# MINIRACER-FMU.net
KiCad netlist of a schematic drawn in Altium Designer
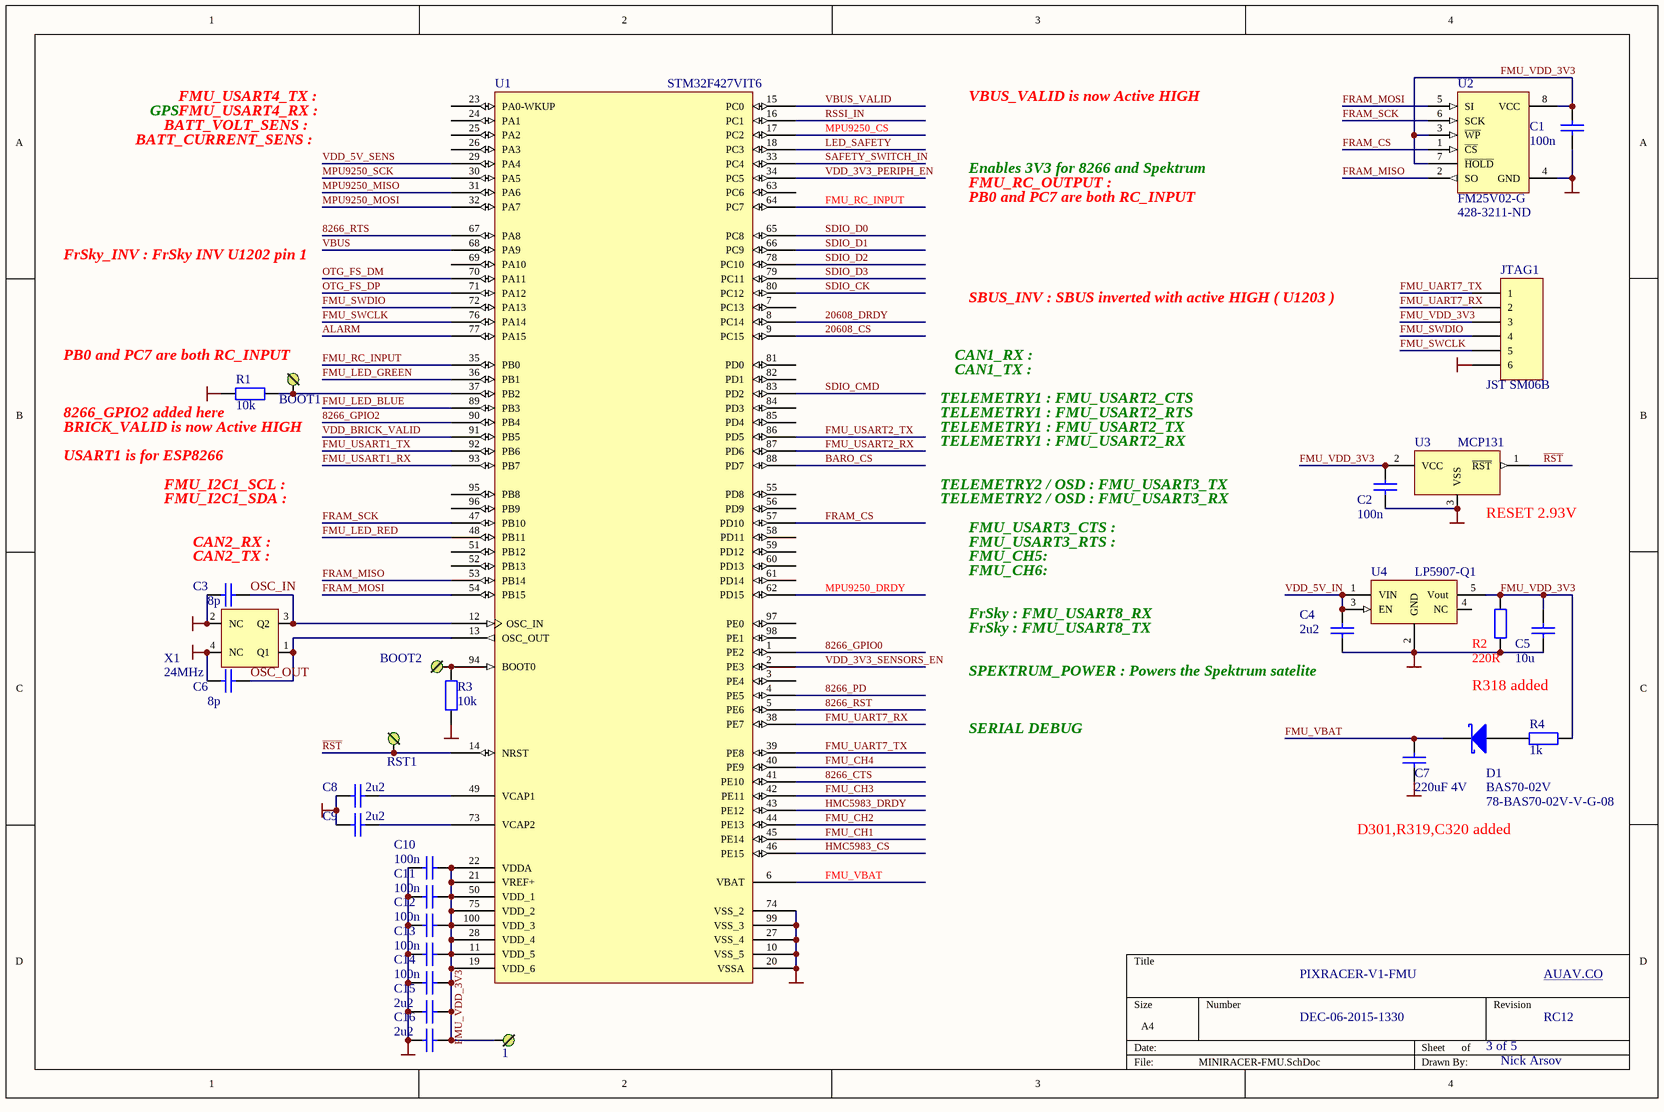
[diagram p0: MINIRACER-FMU.SchDoc]

(export (version "E")
  (design (tool "Eeschema 10.0.6"))
  (components
    (comp (ref "1") (value "3V3") (footprint "PAD1") (libsource (lib "My_Altium") (part "PLUG")))
    (comp (ref "BOOT1") (value "BOOT1") (footprint "PAD1") (libsource (lib "My_Altium") (part "PLUG")))
    (comp (ref "BOOT2") (value "BOOT") (footprint "PAD1") (libsource (lib "My_Altium") (part "PLUG")))
    (comp (ref "C1")
      (value "100n")
      (footprint "0402A")
      (description "Capacitor")
      (fields (field (name "PUBLISHER") "Altium Limited"))
      (libsource (lib "Miscellaneous Devices") (part "Cap"))
    )
    (comp (ref "C2")
      (value "100n")
      (footprint "0402A")
      (description "Capacitor")
      (fields (field (name "PUBLISHER") "Altium Limited"))
      (libsource (lib "Miscellaneous Devices") (part "Cap"))
    )
    (comp (ref "C3")
      (value "8p")
      (footprint "0603A")
      (description "Capacitor")
      (fields (field (name "PUBLISHER") "Altium Limited"))
      (libsource (lib "Miscellaneous Devices") (part "Cap"))
    )
    (comp (ref "C4")
      (value "2u2")
      (footprint "0603A")
      (description "Capacitor")
      (fields (field (name "PUBLISHER") "Altium Limited"))
      (libsource (lib "Miscellaneous Devices") (part "Cap"))
    )
    (comp (ref "C5")
      (value "10u")
      (footprint "0603A")
      (description "Capacitor")
      (fields (field (name "PUBLISHER") "Altium Limited"))
      (libsource (lib "Miscellaneous Devices") (part "Cap"))
    )
    (comp (ref "C6")
      (value "8p")
      (footprint "0603A")
      (description "Capacitor")
      (fields (field (name "PUBLISHER") "Altium Limited"))
      (libsource (lib "Miscellaneous Devices") (part "Cap"))
    )
    (comp (ref "C7")
      (value "220uF 4V")
      (footprint "1206A")
      (description "Capacitor")
      (fields (field (name "PUBLISHER") "Altium Limited"))
      (libsource (lib "Miscellaneous Devices") (part "Cap"))
    )
    (comp (ref "C8")
      (value "2u2")
      (footprint "0402A")
      (description "Capacitor")
      (fields (field (name "PUBLISHER") "Altium Limited"))
      (libsource (lib "Miscellaneous Devices") (part "Cap"))
    )
    (comp (ref "C9")
      (value "2u2")
      (footprint "0402A")
      (description "Capacitor")
      (fields (field (name "PUBLISHER") "Altium Limited"))
      (libsource (lib "Miscellaneous Devices") (part "Cap"))
    )
    (comp (ref "C10")
      (value "100n")
      (footprint "0402A")
      (description "Capacitor")
      (fields (field (name "PUBLISHER") "Altium Limited"))
      (libsource (lib "Miscellaneous Devices") (part "Cap"))
    )
    (comp (ref "C11")
      (value "100n")
      (footprint "0402A")
      (description "Capacitor")
      (fields (field (name "PUBLISHER") "Altium Limited"))
      (libsource (lib "Miscellaneous Devices") (part "Cap"))
    )
    (comp (ref "C12")
      (value "100n")
      (footprint "0402A")
      (description "Capacitor")
      (fields (field (name "PUBLISHER") "Altium Limited"))
      (libsource (lib "Miscellaneous Devices") (part "Cap"))
    )
    (comp (ref "C13")
      (value "100n")
      (footprint "0402A")
      (description "Capacitor")
      (fields (field (name "PUBLISHER") "Altium Limited"))
      (libsource (lib "Miscellaneous Devices") (part "Cap"))
    )
    (comp (ref "C14")
      (value "100n")
      (footprint "0402A")
      (description "Capacitor")
      (fields (field (name "PUBLISHER") "Altium Limited"))
      (libsource (lib "Miscellaneous Devices") (part "Cap"))
    )
    (comp (ref "C15")
      (value "2u2")
      (footprint "0402A")
      (description "Capacitor")
      (fields (field (name "PUBLISHER") "Altium Limited"))
      (libsource (lib "Miscellaneous Devices") (part "Cap"))
    )
    (comp (ref "C16")
      (value "2u2")
      (footprint "0402A")
      (description "Capacitor")
      (fields (field (name "PUBLISHER") "Altium Limited"))
      (libsource (lib "Miscellaneous Devices") (part "Cap"))
    )
    (comp (ref "D1")
      (value "BAS70-02V")
      (footprint "SOD-523")
      (description "Schottky Diode")
      (fields (field (name "MOUSER") "78-BAS70-02V-V-G-08") (field (name "PUBLISHER") "Altium Limited"))
      (libsource (lib "Miscellaneous Devices") (part "D Schottky"))
    )
    (comp (ref "JTAG1")
      (value "JST SM06B")
      (footprint "HDR1X6")
      (description "Header, 6-Pin")
      (fields (field (name "PUBLISHER") "Altium Limited"))
      (libsource (lib "Miscellaneous Connectors") (part "Header 6"))
    )
    (comp (ref "R1")
      (value "10k")
      (footprint "0402A")
      (description "Resistor")
      (fields (field (name "PUBLISHER") "Altium Limited"))
      (libsource (lib "Miscellaneous Devices") (part "Res2"))
    )
    (comp (ref "R2")
      (value "220R")
      (footprint "0603A")
      (description "Resistor")
      (fields (field (name "PUBLISHER") "Altium Limited"))
      (libsource (lib "") (part "Res2_1"))
    )
    (comp (ref "R3")
      (value "10k")
      (footprint "0402A")
      (description "Resistor")
      (fields (field (name "PUBLISHER") "Altium Limited"))
      (libsource (lib "") (part "Res2_2"))
    )
    (comp (ref "R4")
      (value "1k")
      (footprint "0603A")
      (description "Resistor")
      (fields (field (name "PUBLISHER") "Altium Limited"))
      (libsource (lib "") (part "Res2_3"))
    )
    (comp (ref "RST1") (value "BOOT") (footprint "PAD1") (libsource (lib "My_Altium") (part "PLUG")))
    (comp (ref "U1")
      (value "STM32F427VIT6")
      (footprint "LQFP100_L")
      (description "STM32 ARM-based 32-bit MCU with 64 Kbytes Flash, 100-pin LQFP, Industrial Temperature")
      (fields (field (name "PUBLISHER") "Altium Limited"))
      (libsource (lib "ST Microcontroller 32-Bit STM32") (part "STM32F103VBT6"))
    )
    (comp (ref "U2")
      (value "FM25V02-G")
      (footprint "SO-8_N")
      (fields (field (name "SUPPLIER PART NUMBER") "428-3211-ND"))
      (libsource (lib "My_Altium") (part "AT45DB161D-MU"))
    )
    (comp (ref "U3") (value "MCP131") (footprint "SOT-323") (libsource (lib "My_Altium") (part "MCP102")))
    (comp (ref "U4")
      (value "LP5907-Q1")
      (footprint "SOT23-5")
      (libsource (lib "My_Altium") (part "LP5907-Q1"))
    )
    (comp (ref "X1")
      (value "24MHz")
      (footprint "Crystal_2.5x2")
      (libsource (lib "My_Altium") (part "Crystal_4pin"))
    )
  )
  (nets
    (net (code "1") (name "/8266_CTS") (class "Default")
      (node (ref "U1") (pin "41") (pinfunction "PE10_41") (pintype "bidirectional"))
    )
    (net (code "2") (name "/8266_GPIO0") (class "Default")
      (node (ref "U1") (pin "1") (pinfunction "PE2_1") (pintype "bidirectional"))
    )
    (net (code "3") (name "/8266_GPIO2") (class "Default")
      (node (ref "U1") (pin "90") (pinfunction "PB4_90") (pintype "bidirectional"))
    )
    (net (code "4") (name "/8266_PD") (class "Default")
      (node (ref "U1") (pin "4") (pinfunction "PE5_4") (pintype "bidirectional"))
    )
    (net (code "5") (name "/8266_RST") (class "Default")
      (node (ref "U1") (pin "5") (pinfunction "PE6_5") (pintype "bidirectional"))
    )
    (net (code "6") (name "/8266_RTS") (class "Default")
      (node (ref "U1") (pin "67") (pinfunction "PA8_67") (pintype "bidirectional"))
    )
    (net (code "7") (name "/20608_CS") (class "Default")
      (node (ref "U1") (pin "9") (pinfunction "PC15_9") (pintype "bidirectional"))
    )
    (net (code "8") (name "/20608_DRDY") (class "Default")
      (node (ref "U1") (pin "8") (pinfunction "PC14_8") (pintype "bidirectional"))
    )
    (net (code "9") (name "/ALARM") (class "Default")
      (node (ref "U1") (pin "77") (pinfunction "PA15_77") (pintype "bidirectional"))
    )
    (net (code "10") (name "/BARO_CS") (class "Default")
      (node (ref "U1") (pin "88") (pinfunction "PD7_88") (pintype "bidirectional"))
    )
    (net (code "11") (name "/FMU_CH1") (class "Default")
      (node (ref "U1") (pin "45") (pinfunction "PE14_45") (pintype "bidirectional"))
    )
    (net (code "12") (name "/FMU_CH2") (class "Default")
      (node (ref "U1") (pin "44") (pinfunction "PE13_44") (pintype "bidirectional"))
    )
    (net (code "13") (name "/FMU_CH3") (class "Default")
      (node (ref "U1") (pin "42") (pinfunction "PE11_42") (pintype "bidirectional"))
    )
    (net (code "14") (name "/FMU_CH4") (class "Default")
      (node (ref "U1") (pin "40") (pinfunction "PE9_40") (pintype "bidirectional"))
    )
    (net (code "15") (name "/FMU_LED_BLUE") (class "Default")
      (node (ref "U1") (pin "89") (pinfunction "PB3_89") (pintype "bidirectional"))
    )
    (net (code "16") (name "/FMU_LED_GREEN") (class "Default")
      (node (ref "U1") (pin "36") (pinfunction "PB1_36") (pintype "bidirectional"))
    )
    (net (code "17") (name "/FMU_LED_RED") (class "Default")
      (node (ref "U1") (pin "48") (pinfunction "PB11_48") (pintype "bidirectional"))
    )
    (net (code "18") (name "/FMU_RC_INPUT") (class "Default")
      (node (ref "U1") (pin "35") (pinfunction "PB0_35") (pintype "bidirectional"))
      (node (ref "U1") (pin "64") (pinfunction "PC7_64") (pintype "bidirectional"))
    )
    (net (code "19") (name "/FMU_SWCLK") (class "Default")
      (node (ref "JTAG1") (pin "5") (pinfunction "5_5") (pintype "passive"))
      (node (ref "U1") (pin "76") (pinfunction "PA14_76") (pintype "bidirectional"))
    )
    (net (code "20") (name "/FMU_SWDIO") (class "Default")
      (node (ref "JTAG1") (pin "4") (pinfunction "4_4") (pintype "passive"))
      (node (ref "U1") (pin "72") (pinfunction "PA13_72") (pintype "bidirectional"))
    )
    (net (code "21") (name "/FMU_UART7_RX") (class "Default")
      (node (ref "JTAG1") (pin "2") (pinfunction "2_2") (pintype "passive"))
      (node (ref "U1") (pin "38") (pinfunction "PE7_38") (pintype "bidirectional"))
    )
    (net (code "22") (name "/FMU_UART7_TX") (class "Default")
      (node (ref "JTAG1") (pin "1") (pinfunction "1_1") (pintype "passive"))
      (node (ref "U1") (pin "39") (pinfunction "PE8_39") (pintype "bidirectional"))
    )
    (net (code "23") (name "/FMU_USART1_RX") (class "Default")
      (node (ref "U1") (pin "93") (pinfunction "PB7_93") (pintype "bidirectional"))
    )
    (net (code "24") (name "/FMU_USART1_TX") (class "Default")
      (node (ref "U1") (pin "92") (pinfunction "PB6_92") (pintype "bidirectional"))
    )
    (net (code "25") (name "/FMU_USART2_RX") (class "Default")
      (node (ref "U1") (pin "87") (pinfunction "PD6_87") (pintype "bidirectional"))
    )
    (net (code "26") (name "/FMU_USART2_TX") (class "Default")
      (node (ref "U1") (pin "86") (pinfunction "PD5_86") (pintype "bidirectional"))
    )
    (net (code "27") (name "/FMU_VBAT") (class "Default")
      (node (ref "C7") (pin "2") (pinfunction "2_2") (pintype "passive"))
      (node (ref "D1") (pin "2") (pinfunction "K_2") (pintype "passive"))
      (node (ref "U1") (pin "6") (pinfunction "VBAT_6") (pintype "power_in"))
    )
    (net (code "28") (name "/FMU_VDD_3V3") (class "Default")
      (node (ref "1") (pin "1") (pintype "passive"))
      (node (ref "C1") (pin "2") (pinfunction "2_2") (pintype "passive"))
      (node (ref "C10") (pin "2") (pinfunction "2_2") (pintype "passive"))
      (node (ref "C11") (pin "2") (pinfunction "2_2") (pintype "passive"))
      (node (ref "C12") (pin "2") (pinfunction "2_2") (pintype "passive"))
      (node (ref "C13") (pin "2") (pinfunction "2_2") (pintype "passive"))
      (node (ref "C14") (pin "2") (pinfunction "2_2") (pintype "passive"))
      (node (ref "C15") (pin "2") (pinfunction "2_2") (pintype "passive"))
      (node (ref "C16") (pin "2") (pinfunction "2_2") (pintype "passive"))
      (node (ref "C2") (pin "2") (pinfunction "2_2") (pintype "passive"))
      (node (ref "C5") (pin "2") (pinfunction "2_2") (pintype "passive"))
      (node (ref "JTAG1") (pin "3") (pinfunction "3_3") (pintype "passive"))
      (node (ref "R2") (pin "2") (pinfunction "2_2") (pintype "passive"))
      (node (ref "R4") (pin "1") (pinfunction "1_1") (pintype "passive"))
      (node (ref "U1") (pin "100") (pinfunction "VDD_3_100") (pintype "power_in"))
      (node (ref "U1") (pin "11") (pinfunction "VDD_5_11") (pintype "power_in"))
      (node (ref "U1") (pin "19") (pinfunction "VDD_6_19") (pintype "power_in"))
      (node (ref "U1") (pin "21") (pinfunction "VREF+_21") (pintype "power_in"))
      (node (ref "U1") (pin "22") (pinfunction "VDDA_22") (pintype "power_in"))
      (node (ref "U1") (pin "28") (pinfunction "VDD_4_28") (pintype "power_in"))
      (node (ref "U1") (pin "50") (pinfunction "VDD_1_50") (pintype "power_in"))
      (node (ref "U1") (pin "75") (pinfunction "VDD_2_75") (pintype "power_in"))
      (node (ref "U2") (pin "3") (pinfunction "~{WP}_3") (pintype "input"))
      (node (ref "U2") (pin "7") (pinfunction "~{HOLD}_7") (pintype "passive"))
      (node (ref "U2") (pin "8") (pinfunction "VCC_8") (pintype "power_in"))
      (node (ref "U3") (pin "2") (pinfunction "VCC_2") (pintype "power_in"))
      (node (ref "U4") (pin "5") (pinfunction "Vout_5") (pintype "power_in"))
    )
    (net (code "29") (name "/FRAM_CS") (class "Default")
      (node (ref "U1") (pin "57") (pinfunction "PD10_57") (pintype "bidirectional"))
      (node (ref "U2") (pin "1") (pinfunction "~{CS}_1") (pintype "input"))
    )
    (net (code "30") (name "/FRAM_MISO") (class "Default")
      (node (ref "U1") (pin "53") (pinfunction "PB14_53") (pintype "bidirectional"))
      (node (ref "U2") (pin "2") (pinfunction "SO_2") (pintype "output"))
    )
    (net (code "31") (name "/FRAM_MOSI") (class "Default")
      (node (ref "U1") (pin "54") (pinfunction "PB15_54") (pintype "bidirectional"))
      (node (ref "U2") (pin "5") (pinfunction "SI_5") (pintype "input"))
    )
    (net (code "32") (name "/FRAM_SCK") (class "Default")
      (node (ref "U1") (pin "47") (pinfunction "PB10_47") (pintype "bidirectional"))
      (node (ref "U2") (pin "6") (pinfunction "SCK_6") (pintype "input"))
    )
    (net (code "33") (name "/HMC5983_CS") (class "Default")
      (node (ref "U1") (pin "46") (pinfunction "PE15_46") (pintype "bidirectional"))
    )
    (net (code "34") (name "/HMC5983_DRDY") (class "Default")
      (node (ref "U1") (pin "43") (pinfunction "PE12_43") (pintype "bidirectional"))
    )
    (net (code "35") (name "/LED_SAFETY") (class "Default")
      (node (ref "U1") (pin "18") (pinfunction "PC3_18") (pintype "bidirectional"))
    )
    (net (code "36") (name "/MPU9250_CS") (class "Default")
      (node (ref "U1") (pin "17") (pinfunction "PC2_17") (pintype "bidirectional"))
    )
    (net (code "37") (name "/MPU9250_DRDY") (class "Default")
      (node (ref "U1") (pin "62") (pinfunction "PD15_62") (pintype "bidirectional"))
    )
    (net (code "38") (name "/MPU9250_MISO") (class "Default")
      (node (ref "U1") (pin "31") (pinfunction "PA6_31") (pintype "bidirectional"))
    )
    (net (code "39") (name "/MPU9250_MOSI") (class "Default")
      (node (ref "U1") (pin "32") (pinfunction "PA7_32") (pintype "bidirectional"))
    )
    (net (code "40") (name "/MPU9250_SCK") (class "Default")
      (node (ref "U1") (pin "30") (pinfunction "PA5_30") (pintype "bidirectional"))
    )
    (net (code "41") (name "/OSC_IN") (class "Default")
      (node (ref "C3") (pin "2") (pinfunction "2_2") (pintype "passive"))
      (node (ref "U1") (pin "12") (pinfunction "OSC_IN_12") (pintype "input"))
      (node (ref "X1") (pin "3") (pinfunction "Q2_3") (pintype "passive"))
    )
    (net (code "42") (name "/OSC_OUT") (class "Default")
      (node (ref "C6") (pin "2") (pinfunction "2_2") (pintype "passive"))
      (node (ref "U1") (pin "13") (pinfunction "OSC_OUT_13") (pintype "output"))
      (node (ref "X1") (pin "1") (pinfunction "Q1_1") (pintype "passive"))
    )
    (net (code "43") (name "/OTG_FS_DM") (class "Default")
      (node (ref "U1") (pin "70") (pinfunction "PA11_70") (pintype "bidirectional"))
    )
    (net (code "44") (name "/OTG_FS_DP") (class "Default")
      (node (ref "U1") (pin "71") (pinfunction "PA12_71") (pintype "bidirectional"))
    )
    (net (code "45") (name "/RSSI_IN") (class "Default")
      (node (ref "U1") (pin "16") (pinfunction "PC1_16") (pintype "bidirectional"))
    )
    (net (code "46") (name "/SAFETY_SWITCH_IN") (class "Default")
      (node (ref "U1") (pin "33") (pinfunction "PC4_33") (pintype "bidirectional"))
    )
    (net (code "47") (name "/SDIO_CK") (class "Default")
      (node (ref "U1") (pin "80") (pinfunction "PC12_80") (pintype "bidirectional"))
    )
    (net (code "48") (name "/SDIO_CMD") (class "Default")
      (node (ref "U1") (pin "83") (pinfunction "PD2_83") (pintype "bidirectional"))
    )
    (net (code "49") (name "/SDIO_D0") (class "Default")
      (node (ref "U1") (pin "65") (pinfunction "PC8_65") (pintype "bidirectional"))
    )
    (net (code "50") (name "/SDIO_D1") (class "Default")
      (node (ref "U1") (pin "66") (pinfunction "PC9_66") (pintype "bidirectional"))
    )
    (net (code "51") (name "/SDIO_D2") (class "Default")
      (node (ref "U1") (pin "78") (pinfunction "PC10_78") (pintype "bidirectional"))
    )
    (net (code "52") (name "/SDIO_D3") (class "Default")
      (node (ref "U1") (pin "79") (pinfunction "PC11_79") (pintype "bidirectional"))
    )
    (net (code "53") (name "/VBUS") (class "Default")
      (node (ref "U1") (pin "68") (pinfunction "PA9_68") (pintype "bidirectional"))
    )
    (net (code "54") (name "/VBUS_VALID") (class "Default")
      (node (ref "U1") (pin "15") (pinfunction "PC0_15") (pintype "bidirectional"))
    )
    (net (code "55") (name "/VDD_3V3_PERIPH_EN") (class "Default")
      (node (ref "U1") (pin "34") (pinfunction "PC5_34") (pintype "bidirectional"))
    )
    (net (code "56") (name "/VDD_3V3_SENSORS_EN") (class "Default")
      (node (ref "U1") (pin "2") (pinfunction "PE3_2") (pintype "bidirectional"))
    )
    (net (code "57") (name "/VDD_5V_IN") (class "Default")
      (node (ref "C4") (pin "2") (pinfunction "2_2") (pintype "passive"))
      (node (ref "U4") (pin "1") (pinfunction "VIN_1") (pintype "power_in"))
      (node (ref "U4") (pin "3") (pinfunction "EN_3") (pintype "input"))
    )
    (net (code "58") (name "/VDD_5V_SENS") (class "Default")
      (node (ref "U1") (pin "29") (pinfunction "PA4_29") (pintype "bidirectional"))
    )
    (net (code "59") (name "/VDD_BRICK_VALID") (class "Default")
      (node (ref "U1") (pin "91") (pinfunction "PB5_91") (pintype "bidirectional"))
    )
    (net (code "60") (name "/~{RST}") (class "Default")
      (node (ref "RST1") (pin "1") (pintype "passive"))
      (node (ref "U1") (pin "14") (pinfunction "NRST_14") (pintype "bidirectional"))
      (node (ref "U3") (pin "1") (pinfunction "~{RST}_1") (pintype "output"))
    )
    (net (code "61") (name "GND") (class "Default")
      (node (ref "C1") (pin "1") (pinfunction "1_1") (pintype "passive"))
      (node (ref "C10") (pin "1") (pinfunction "1_1") (pintype "passive"))
      (node (ref "C11") (pin "1") (pinfunction "1_1") (pintype "passive"))
      (node (ref "C12") (pin "1") (pinfunction "1_1") (pintype "passive"))
      (node (ref "C13") (pin "1") (pinfunction "1_1") (pintype "passive"))
      (node (ref "C14") (pin "1") (pinfunction "1_1") (pintype "passive"))
      (node (ref "C15") (pin "1") (pinfunction "1_1") (pintype "passive"))
      (node (ref "C16") (pin "1") (pinfunction "1_1") (pintype "passive"))
      (node (ref "C2") (pin "1") (pinfunction "1_1") (pintype "passive"))
      (node (ref "C3") (pin "1") (pinfunction "1_1") (pintype "passive"))
      (node (ref "C4") (pin "1") (pinfunction "1_1") (pintype "passive"))
      (node (ref "C5") (pin "1") (pinfunction "1_1") (pintype "passive"))
      (node (ref "C6") (pin "1") (pinfunction "1_1") (pintype "passive"))
      (node (ref "C7") (pin "1") (pinfunction "1_1") (pintype "passive"))
      (node (ref "C8") (pin "2") (pinfunction "2_2") (pintype "passive"))
      (node (ref "C9") (pin "2") (pinfunction "2_2") (pintype "passive"))
      (node (ref "JTAG1") (pin "6") (pinfunction "6_6") (pintype "passive"))
      (node (ref "R1") (pin "1") (pinfunction "1_1") (pintype "passive"))
      (node (ref "R2") (pin "1") (pinfunction "1_1") (pintype "passive"))
      (node (ref "R3") (pin "2") (pinfunction "2_2") (pintype "passive"))
      (node (ref "U1") (pin "10") (pinfunction "VSS_5_10") (pintype "power_in"))
      (node (ref "U1") (pin "20") (pinfunction "VSSA_20") (pintype "power_in"))
      (node (ref "U1") (pin "27") (pinfunction "VSS_4_27") (pintype "power_in"))
      (node (ref "U1") (pin "74") (pinfunction "VSS_2_74") (pintype "power_in"))
      (node (ref "U1") (pin "99") (pinfunction "VSS_3_99") (pintype "power_in"))
      (node (ref "U2") (pin "4") (pinfunction "GND_4") (pintype "power_in"))
      (node (ref "U3") (pin "3") (pinfunction "VSS_3") (pintype "power_in"))
      (node (ref "U4") (pin "2") (pinfunction "GND_2") (pintype "power_in"))
      (node (ref "X1") (pin "2") (pinfunction "NC_2") (pintype "passive"))
      (node (ref "X1") (pin "4") (pinfunction "NC_4") (pintype "passive"))
    )
    (net (code "62") (name "Net-(D1-A)") (class "Default")
      (node (ref "D1") (pin "1") (pinfunction "A_1") (pintype "passive"))
      (node (ref "R4") (pin "2") (pinfunction "2_2") (pintype "passive"))
    )
    (net (code "63") (name "Net-(U1-BOOT0)") (class "Default")
      (node (ref "BOOT2") (pin "1") (pintype "passive"))
      (node (ref "R3") (pin "1") (pinfunction "1_1") (pintype "passive"))
      (node (ref "U1") (pin "94") (pinfunction "BOOT0_94") (pintype "input"))
    )
    (net (code "64") (name "Net-(U1-PB2)") (class "Default")
      (node (ref "BOOT1") (pin "1") (pintype "passive"))
      (node (ref "R1") (pin "2") (pinfunction "2_2") (pintype "passive"))
      (node (ref "U1") (pin "37") (pinfunction "PB2_37") (pintype "bidirectional"))
    )
    (net (code "65") (name "Net-(U1-VCAP1)") (class "Default")
      (node (ref "C8") (pin "1") (pinfunction "1_1") (pintype "passive"))
      (node (ref "U1") (pin "49") (pinfunction "VCAP1_49") (pintype "passive"))
    )
    (net (code "66") (name "Net-(U1-VCAP2)") (class "Default")
      (node (ref "C9") (pin "1") (pinfunction "1_1") (pintype "passive"))
      (node (ref "U1") (pin "73") (pinfunction "VCAP2_73") (pintype "passive"))
    )
    (net (code "67") (name "unconnected-(U1-PA0-WKUP-Pad23)") (class "Default")
      (node (ref "U1") (pin "23") (pinfunction "PA0-WKUP_23") (pintype "bidirectional"))
    )
    (net (code "68") (name "unconnected-(U1-PA1-Pad24)") (class "Default")
      (node (ref "U1") (pin "24") (pinfunction "PA1_24") (pintype "bidirectional"))
    )
    (net (code "69") (name "unconnected-(U1-PA2-Pad25)") (class "Default")
      (node (ref "U1") (pin "25") (pinfunction "PA2_25") (pintype "bidirectional"))
    )
    (net (code "70") (name "unconnected-(U1-PA3-Pad26)") (class "Default")
      (node (ref "U1") (pin "26") (pinfunction "PA3_26") (pintype "bidirectional"))
    )
    (net (code "71") (name "unconnected-(U1-PA10-Pad69)") (class "Default")
      (node (ref "U1") (pin "69") (pinfunction "PA10_69") (pintype "bidirectional"))
    )
    (net (code "72") (name "unconnected-(U1-PB8-Pad95)") (class "Default")
      (node (ref "U1") (pin "95") (pinfunction "PB8_95") (pintype "bidirectional"))
    )
    (net (code "73") (name "unconnected-(U1-PB9-Pad96)") (class "Default")
      (node (ref "U1") (pin "96") (pinfunction "PB9_96") (pintype "bidirectional"))
    )
    (net (code "74") (name "unconnected-(U1-PB12-Pad51)") (class "Default")
      (node (ref "U1") (pin "51") (pinfunction "PB12_51") (pintype "bidirectional"))
    )
    (net (code "75") (name "unconnected-(U1-PB13-Pad52)") (class "Default")
      (node (ref "U1") (pin "52") (pinfunction "PB13_52") (pintype "bidirectional"))
    )
    (net (code "76") (name "unconnected-(U1-PC6-Pad63)") (class "Default")
      (node (ref "U1") (pin "63") (pinfunction "PC6_63") (pintype "bidirectional"))
    )
    (net (code "77") (name "unconnected-(U1-PC13-Pad7)") (class "Default")
      (node (ref "U1") (pin "7") (pinfunction "PC13_7") (pintype "bidirectional"))
    )
    (net (code "78") (name "unconnected-(U1-PD0-Pad81)") (class "Default")
      (node (ref "U1") (pin "81") (pinfunction "PD0_81") (pintype "bidirectional"))
    )
    (net (code "79") (name "unconnected-(U1-PD1-Pad82)") (class "Default")
      (node (ref "U1") (pin "82") (pinfunction "PD1_82") (pintype "bidirectional"))
    )
    (net (code "80") (name "unconnected-(U1-PD3-Pad84)") (class "Default")
      (node (ref "U1") (pin "84") (pinfunction "PD3_84") (pintype "bidirectional"))
    )
    (net (code "81") (name "unconnected-(U1-PD4-Pad85)") (class "Default")
      (node (ref "U1") (pin "85") (pinfunction "PD4_85") (pintype "bidirectional"))
    )
    (net (code "82") (name "unconnected-(U1-PD8-Pad55)") (class "Default")
      (node (ref "U1") (pin "55") (pinfunction "PD8_55") (pintype "bidirectional"))
    )
    (net (code "83") (name "unconnected-(U1-PD9-Pad56)") (class "Default")
      (node (ref "U1") (pin "56") (pinfunction "PD9_56") (pintype "bidirectional"))
    )
    (net (code "84") (name "unconnected-(U1-PD11-Pad58)") (class "Default")
      (node (ref "U1") (pin "58") (pinfunction "PD11_58") (pintype "bidirectional"))
    )
    (net (code "85") (name "unconnected-(U1-PD12-Pad59)") (class "Default")
      (node (ref "U1") (pin "59") (pinfunction "PD12_59") (pintype "bidirectional"))
    )
    (net (code "86") (name "unconnected-(U1-PD13-Pad60)") (class "Default")
      (node (ref "U1") (pin "60") (pinfunction "PD13_60") (pintype "bidirectional"))
    )
    (net (code "87") (name "unconnected-(U1-PD14-Pad61)") (class "Default")
      (node (ref "U1") (pin "61") (pinfunction "PD14_61") (pintype "bidirectional"))
    )
    (net (code "88") (name "unconnected-(U1-PE0-Pad97)") (class "Default")
      (node (ref "U1") (pin "97") (pinfunction "PE0_97") (pintype "bidirectional"))
    )
    (net (code "89") (name "unconnected-(U1-PE1-Pad98)") (class "Default")
      (node (ref "U1") (pin "98") (pinfunction "PE1_98") (pintype "bidirectional"))
    )
    (net (code "90") (name "unconnected-(U1-PE4-Pad3)") (class "Default")
      (node (ref "U1") (pin "3") (pinfunction "PE4_3") (pintype "bidirectional"))
    )
    (net (code "91") (name "unconnected-(U4-NC-Pad4)") (class "Default")
      (node (ref "U4") (pin "4") (pinfunction "NC_4") (pintype "passive"))
    )
  )
)
